# NEB_SRAM.net
KiCad netlist of a schematic drawn in Altium Designer
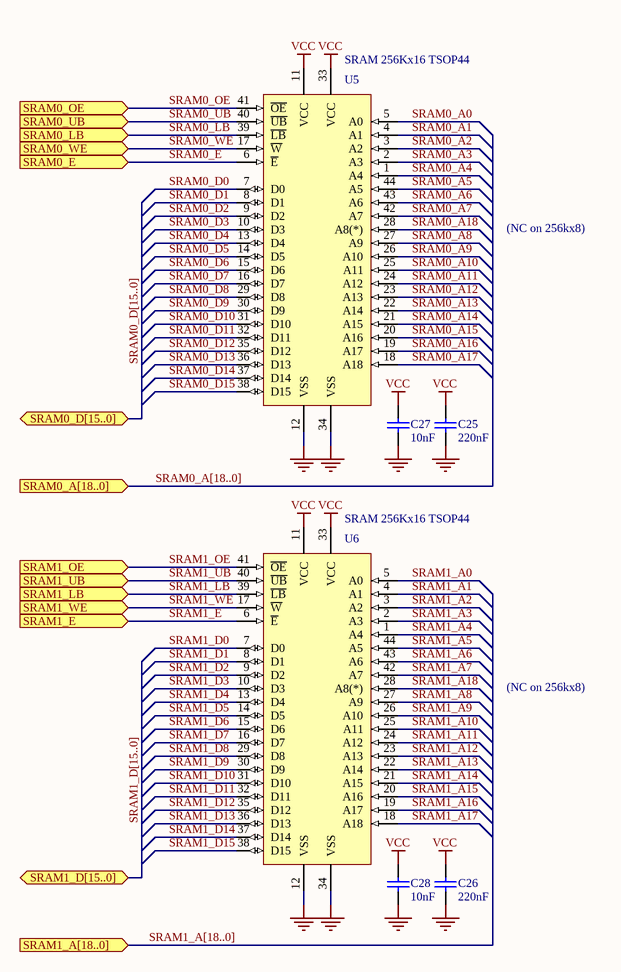
[diagram p0: NEB_SRAM.SchDoc]

(export (version "E")
  (design (tool "Eeschema 10.0.6"))
  (components
    (comp (ref "C25")
      (value "220nF")
      (footprint "CC2012-0805")
      (description "Capacitor")
      (libsource (lib "PassiveSMD") (part "CAP"))
    )
    (comp (ref "C26")
      (value "220nF")
      (footprint "CC2012-0805")
      (description "Capacitor")
      (libsource (lib "PassiveSMD") (part "CAP"))
    )
    (comp (ref "C27")
      (value "10nF")
      (footprint "CC2012-0805")
      (description "Capacitor")
      (libsource (lib "PassiveSMD") (part "CAP"))
    )
    (comp (ref "C28")
      (value "10nF")
      (footprint "CC2012-0805")
      (description "Capacitor")
      (libsource (lib "PassiveSMD") (part "CAP"))
    )
    (comp (ref "U5")
      (value "SRAM 256Kx16 TSOP44")
      (footprint "SO-G44/P.8")
      (description "512Kx16Bit SRAM TSOP44")
      (libsource (lib "ChrisSchematic") (part "SRAM 512Kx16 TSOP44"))
    )
    (comp (ref "U6")
      (value "SRAM 256Kx16 TSOP44")
      (footprint "SO-G44/P.8")
      (description "512Kx16Bit SRAM TSOP44")
      (libsource (lib "ChrisSchematic") (part "SRAM 512Kx16 TSOP44"))
    )
  )
  (nets
    (net (code "1") (name "/SRAM0_A0") (class "Default")
      (node (ref "U5") (pin "5") (pinfunction "A0_5") (pintype "input"))
    )
    (net (code "2") (name "/SRAM0_A1") (class "Default")
      (node (ref "U5") (pin "4") (pinfunction "A1_4") (pintype "input"))
    )
    (net (code "3") (name "/SRAM0_A2") (class "Default")
      (node (ref "U5") (pin "3") (pinfunction "A2_3") (pintype "input"))
    )
    (net (code "4") (name "/SRAM0_A3") (class "Default")
      (node (ref "U5") (pin "2") (pinfunction "A3_2") (pintype "input"))
    )
    (net (code "5") (name "/SRAM0_A4") (class "Default")
      (node (ref "U5") (pin "1") (pinfunction "A4_1") (pintype "input"))
    )
    (net (code "6") (name "/SRAM0_A5") (class "Default")
      (node (ref "U5") (pin "44") (pinfunction "A5_44") (pintype "input"))
    )
    (net (code "7") (name "/SRAM0_A6") (class "Default")
      (node (ref "U5") (pin "43") (pinfunction "A6_43") (pintype "input"))
    )
    (net (code "8") (name "/SRAM0_A7") (class "Default")
      (node (ref "U5") (pin "42") (pinfunction "A7_42") (pintype "input"))
    )
    (net (code "9") (name "/SRAM0_A8") (class "Default")
      (node (ref "U5") (pin "27") (pinfunction "A9_27") (pintype "input"))
    )
    (net (code "10") (name "/SRAM0_A9") (class "Default")
      (node (ref "U5") (pin "26") (pinfunction "A10_26") (pintype "input"))
    )
    (net (code "11") (name "/SRAM0_A10") (class "Default")
      (node (ref "U5") (pin "25") (pinfunction "A11_25") (pintype "input"))
    )
    (net (code "12") (name "/SRAM0_A11") (class "Default")
      (node (ref "U5") (pin "24") (pinfunction "A12_24") (pintype "input"))
    )
    (net (code "13") (name "/SRAM0_A12") (class "Default")
      (node (ref "U5") (pin "23") (pinfunction "A13_23") (pintype "input"))
    )
    (net (code "14") (name "/SRAM0_A13") (class "Default")
      (node (ref "U5") (pin "22") (pinfunction "A14_22") (pintype "input"))
    )
    (net (code "15") (name "/SRAM0_A14") (class "Default")
      (node (ref "U5") (pin "21") (pinfunction "A15_21") (pintype "input"))
    )
    (net (code "16") (name "/SRAM0_A15") (class "Default")
      (node (ref "U5") (pin "20") (pinfunction "A16_20") (pintype "input"))
    )
    (net (code "17") (name "/SRAM0_A16") (class "Default")
      (node (ref "U5") (pin "19") (pinfunction "A17_19") (pintype "input"))
    )
    (net (code "18") (name "/SRAM0_A17") (class "Default")
      (node (ref "U5") (pin "18") (pinfunction "A18_18") (pintype "input"))
    )
    (net (code "19") (name "/SRAM0_A18") (class "Default")
      (node (ref "U5") (pin "28") (pinfunction "A8(*)_28") (pintype "input"))
    )
    (net (code "21") (name "/SRAM0_D0") (class "Default")
      (node (ref "U5") (pin "7") (pinfunction "D0_7") (pintype "bidirectional"))
    )
    (net (code "22") (name "/SRAM0_D1") (class "Default")
      (node (ref "U5") (pin "8") (pinfunction "D1_8") (pintype "bidirectional"))
    )
    (net (code "23") (name "/SRAM0_D2") (class "Default")
      (node (ref "U5") (pin "9") (pinfunction "D2_9") (pintype "bidirectional"))
    )
    (net (code "24") (name "/SRAM0_D3") (class "Default")
      (node (ref "U5") (pin "10") (pinfunction "D3_10") (pintype "bidirectional"))
    )
    (net (code "25") (name "/SRAM0_D4") (class "Default")
      (node (ref "U5") (pin "13") (pinfunction "D4_13") (pintype "bidirectional"))
    )
    (net (code "26") (name "/SRAM0_D5") (class "Default")
      (node (ref "U5") (pin "14") (pinfunction "D5_14") (pintype "bidirectional"))
    )
    (net (code "27") (name "/SRAM0_D6") (class "Default")
      (node (ref "U5") (pin "15") (pinfunction "D6_15") (pintype "bidirectional"))
    )
    (net (code "28") (name "/SRAM0_D7") (class "Default")
      (node (ref "U5") (pin "16") (pinfunction "D7_16") (pintype "bidirectional"))
    )
    (net (code "29") (name "/SRAM0_D8") (class "Default")
      (node (ref "U5") (pin "29") (pinfunction "D8_29") (pintype "bidirectional"))
    )
    (net (code "30") (name "/SRAM0_D9") (class "Default")
      (node (ref "U5") (pin "30") (pinfunction "D9_30") (pintype "bidirectional"))
    )
    (net (code "31") (name "/SRAM0_D10") (class "Default")
      (node (ref "U5") (pin "31") (pinfunction "D10_31") (pintype "bidirectional"))
    )
    (net (code "32") (name "/SRAM0_D11") (class "Default")
      (node (ref "U5") (pin "32") (pinfunction "D11_32") (pintype "bidirectional"))
    )
    (net (code "33") (name "/SRAM0_D12") (class "Default")
      (node (ref "U5") (pin "35") (pinfunction "D12_35") (pintype "bidirectional"))
    )
    (net (code "34") (name "/SRAM0_D13") (class "Default")
      (node (ref "U5") (pin "36") (pinfunction "D13_36") (pintype "bidirectional"))
    )
    (net (code "35") (name "/SRAM0_D14") (class "Default")
      (node (ref "U5") (pin "37") (pinfunction "D14_37") (pintype "bidirectional"))
    )
    (net (code "36") (name "/SRAM0_D15") (class "Default")
      (node (ref "U5") (pin "38") (pinfunction "D15_38") (pintype "bidirectional"))
    )
    (net (code "38") (name "/SRAM0_E") (class "Default")
      (node (ref "U5") (pin "6") (pinfunction "~{E}_6") (pintype "input"))
    )
    (net (code "39") (name "/SRAM0_LB") (class "Default")
      (node (ref "U5") (pin "39") (pinfunction "~{LB}_39") (pintype "input"))
    )
    (net (code "40") (name "/SRAM0_OE") (class "Default")
      (node (ref "U5") (pin "41") (pinfunction "~{OE}_41") (pintype "input"))
    )
    (net (code "41") (name "/SRAM0_UB") (class "Default")
      (node (ref "U5") (pin "40") (pinfunction "~{UB}_40") (pintype "input"))
    )
    (net (code "42") (name "/SRAM0_WE") (class "Default")
      (node (ref "U5") (pin "17") (pinfunction "~{W}_17") (pintype "input"))
    )
    (net (code "43") (name "/SRAM1_A0") (class "Default")
      (node (ref "U6") (pin "5") (pinfunction "A0_5") (pintype "input"))
    )
    (net (code "44") (name "/SRAM1_A1") (class "Default")
      (node (ref "U6") (pin "4") (pinfunction "A1_4") (pintype "input"))
    )
    (net (code "45") (name "/SRAM1_A2") (class "Default")
      (node (ref "U6") (pin "3") (pinfunction "A2_3") (pintype "input"))
    )
    (net (code "46") (name "/SRAM1_A3") (class "Default")
      (node (ref "U6") (pin "2") (pinfunction "A3_2") (pintype "input"))
    )
    (net (code "47") (name "/SRAM1_A4") (class "Default")
      (node (ref "U6") (pin "1") (pinfunction "A4_1") (pintype "input"))
    )
    (net (code "48") (name "/SRAM1_A5") (class "Default")
      (node (ref "U6") (pin "44") (pinfunction "A5_44") (pintype "input"))
    )
    (net (code "49") (name "/SRAM1_A6") (class "Default")
      (node (ref "U6") (pin "43") (pinfunction "A6_43") (pintype "input"))
    )
    (net (code "50") (name "/SRAM1_A7") (class "Default")
      (node (ref "U6") (pin "42") (pinfunction "A7_42") (pintype "input"))
    )
    (net (code "51") (name "/SRAM1_A8") (class "Default")
      (node (ref "U6") (pin "27") (pinfunction "A9_27") (pintype "input"))
    )
    (net (code "52") (name "/SRAM1_A9") (class "Default")
      (node (ref "U6") (pin "26") (pinfunction "A10_26") (pintype "input"))
    )
    (net (code "53") (name "/SRAM1_A10") (class "Default")
      (node (ref "U6") (pin "25") (pinfunction "A11_25") (pintype "input"))
    )
    (net (code "54") (name "/SRAM1_A11") (class "Default")
      (node (ref "U6") (pin "24") (pinfunction "A12_24") (pintype "input"))
    )
    (net (code "55") (name "/SRAM1_A12") (class "Default")
      (node (ref "U6") (pin "23") (pinfunction "A13_23") (pintype "input"))
    )
    (net (code "56") (name "/SRAM1_A13") (class "Default")
      (node (ref "U6") (pin "22") (pinfunction "A14_22") (pintype "input"))
    )
    (net (code "57") (name "/SRAM1_A14") (class "Default")
      (node (ref "U6") (pin "21") (pinfunction "A15_21") (pintype "input"))
    )
    (net (code "58") (name "/SRAM1_A15") (class "Default")
      (node (ref "U6") (pin "20") (pinfunction "A16_20") (pintype "input"))
    )
    (net (code "59") (name "/SRAM1_A16") (class "Default")
      (node (ref "U6") (pin "19") (pinfunction "A17_19") (pintype "input"))
    )
    (net (code "60") (name "/SRAM1_A17") (class "Default")
      (node (ref "U6") (pin "18") (pinfunction "A18_18") (pintype "input"))
    )
    (net (code "61") (name "/SRAM1_A18") (class "Default")
      (node (ref "U6") (pin "28") (pinfunction "A8(*)_28") (pintype "input"))
    )
    (net (code "63") (name "/SRAM1_D0") (class "Default")
      (node (ref "U6") (pin "7") (pinfunction "D0_7") (pintype "bidirectional"))
    )
    (net (code "64") (name "/SRAM1_D1") (class "Default")
      (node (ref "U6") (pin "8") (pinfunction "D1_8") (pintype "bidirectional"))
    )
    (net (code "65") (name "/SRAM1_D2") (class "Default")
      (node (ref "U6") (pin "9") (pinfunction "D2_9") (pintype "bidirectional"))
    )
    (net (code "66") (name "/SRAM1_D3") (class "Default")
      (node (ref "U6") (pin "10") (pinfunction "D3_10") (pintype "bidirectional"))
    )
    (net (code "67") (name "/SRAM1_D4") (class "Default")
      (node (ref "U6") (pin "13") (pinfunction "D4_13") (pintype "bidirectional"))
    )
    (net (code "68") (name "/SRAM1_D5") (class "Default")
      (node (ref "U6") (pin "14") (pinfunction "D5_14") (pintype "bidirectional"))
    )
    (net (code "69") (name "/SRAM1_D6") (class "Default")
      (node (ref "U6") (pin "15") (pinfunction "D6_15") (pintype "bidirectional"))
    )
    (net (code "70") (name "/SRAM1_D7") (class "Default")
      (node (ref "U6") (pin "16") (pinfunction "D7_16") (pintype "bidirectional"))
    )
    (net (code "71") (name "/SRAM1_D8") (class "Default")
      (node (ref "U6") (pin "29") (pinfunction "D8_29") (pintype "bidirectional"))
    )
    (net (code "72") (name "/SRAM1_D9") (class "Default")
      (node (ref "U6") (pin "30") (pinfunction "D9_30") (pintype "bidirectional"))
    )
    (net (code "73") (name "/SRAM1_D10") (class "Default")
      (node (ref "U6") (pin "31") (pinfunction "D10_31") (pintype "bidirectional"))
    )
    (net (code "74") (name "/SRAM1_D11") (class "Default")
      (node (ref "U6") (pin "32") (pinfunction "D11_32") (pintype "bidirectional"))
    )
    (net (code "75") (name "/SRAM1_D12") (class "Default")
      (node (ref "U6") (pin "35") (pinfunction "D12_35") (pintype "bidirectional"))
    )
    (net (code "76") (name "/SRAM1_D13") (class "Default")
      (node (ref "U6") (pin "36") (pinfunction "D13_36") (pintype "bidirectional"))
    )
    (net (code "77") (name "/SRAM1_D14") (class "Default")
      (node (ref "U6") (pin "37") (pinfunction "D14_37") (pintype "bidirectional"))
    )
    (net (code "78") (name "/SRAM1_D15") (class "Default")
      (node (ref "U6") (pin "38") (pinfunction "D15_38") (pintype "bidirectional"))
    )
    (net (code "80") (name "/SRAM1_E") (class "Default")
      (node (ref "U6") (pin "6") (pinfunction "~{E}_6") (pintype "input"))
    )
    (net (code "81") (name "/SRAM1_LB") (class "Default")
      (node (ref "U6") (pin "39") (pinfunction "~{LB}_39") (pintype "input"))
    )
    (net (code "82") (name "/SRAM1_OE") (class "Default")
      (node (ref "U6") (pin "41") (pinfunction "~{OE}_41") (pintype "input"))
    )
    (net (code "83") (name "/SRAM1_UB") (class "Default")
      (node (ref "U6") (pin "40") (pinfunction "~{UB}_40") (pintype "input"))
    )
    (net (code "84") (name "/SRAM1_WE") (class "Default")
      (node (ref "U6") (pin "17") (pinfunction "~{W}_17") (pintype "input"))
    )
    (net (code "85") (name "GND") (class "Default")
      (node (ref "C25") (pin "1") (pinfunction "1_1") (pintype "passive"))
      (node (ref "C26") (pin "1") (pinfunction "1_1") (pintype "passive"))
      (node (ref "C27") (pin "1") (pinfunction "1_1") (pintype "passive"))
      (node (ref "C28") (pin "1") (pinfunction "1_1") (pintype "passive"))
      (node (ref "U5") (pin "12") (pinfunction "VSS_12") (pintype "power_in"))
      (node (ref "U5") (pin "34") (pinfunction "VSS_34") (pintype "power_in"))
      (node (ref "U6") (pin "12") (pinfunction "VSS_12") (pintype "power_in"))
      (node (ref "U6") (pin "34") (pinfunction "VSS_34") (pintype "power_in"))
    )
    (net (code "86") (name "VCC") (class "Default")
      (node (ref "C25") (pin "2") (pinfunction "2_2") (pintype "passive"))
      (node (ref "C26") (pin "2") (pinfunction "2_2") (pintype "passive"))
      (node (ref "C27") (pin "2") (pinfunction "2_2") (pintype "passive"))
      (node (ref "C28") (pin "2") (pinfunction "2_2") (pintype "passive"))
      (node (ref "U5") (pin "11") (pinfunction "VCC_11") (pintype "power_in"))
      (node (ref "U5") (pin "33") (pinfunction "VCC_33") (pintype "power_in"))
      (node (ref "U6") (pin "11") (pinfunction "VCC_11") (pintype "power_in"))
      (node (ref "U6") (pin "33") (pinfunction "VCC_33") (pintype "power_in"))
    )
  )
)
